# me433_test.net
KiCad netlist of a schematic drawn in EAGLE
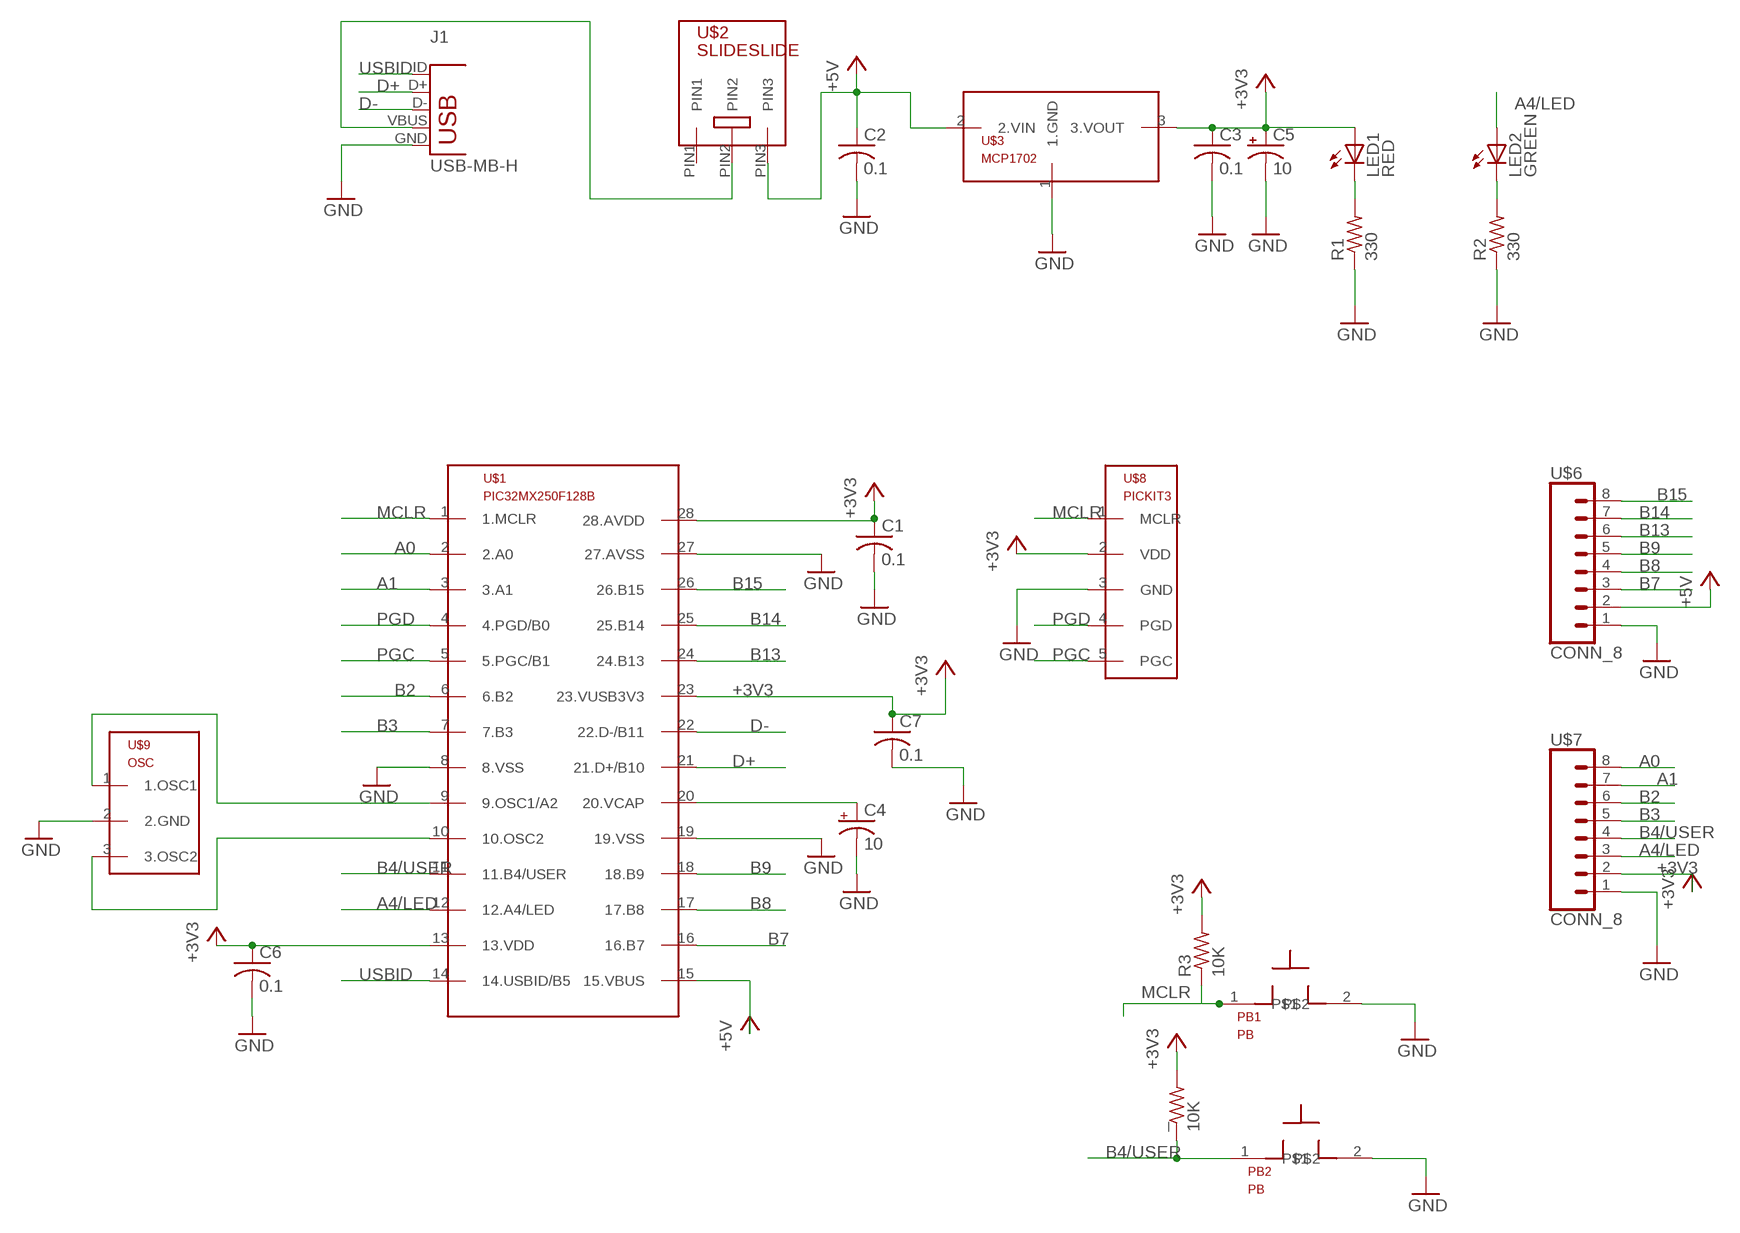
[diagram p0: schematic, sheet 1]

(export (version "E")
  (design (tool "Eeschema 10.0.6"))
  (components
    (comp (ref "C1")
      (value "0.1")
      (footprint "eagle-import:C025-025X050")
      (libsource (lib "eagle-import") (part "C-US025-025X050"))
    )
    (comp (ref "C2")
      (value "0.1")
      (footprint "eagle-import:C025-025X050")
      (libsource (lib "eagle-import") (part "C-US025-025X050"))
    )
    (comp (ref "C3")
      (value "0.1")
      (footprint "eagle-import:C025-025X050")
      (libsource (lib "eagle-import") (part "C-US025-025X050"))
    )
    (comp (ref "C4")
      (value "10")
      (footprint "eagle-import:B45181B")
      (libsource (lib "eagle-import") (part "CPOL-USB45181B"))
    )
    (comp (ref "C5")
      (value "10")
      (footprint "eagle-import:B45181B")
      (libsource (lib "eagle-import") (part "CPOL-USB45181B"))
    )
    (comp (ref "C6")
      (value "0.1")
      (footprint "eagle-import:C025-025X050")
      (libsource (lib "eagle-import") (part "C-US025-025X050"))
    )
    (comp (ref "C7")
      (value "0.1")
      (footprint "eagle-import:C025-025X050")
      (libsource (lib "eagle-import") (part "C-US025-025X050"))
    )
    (comp (ref "J1")
      (value "USB-MB-H")
      (footprint "eagle-import:USB-MB-H")
      (libsource (lib "eagle-import") (part "USB-MB-H"))
    )
    (comp (ref "LED1")
      (value "RED")
      (footprint "eagle-import:LED3MM")
      (libsource (lib "eagle-import") (part "LED3MM"))
    )
    (comp (ref "LED2")
      (value "GREEN")
      (footprint "eagle-import:LED3MM")
      (libsource (lib "eagle-import") (part "LED3MM"))
    )
    (comp (ref "PB1") (value "PB") (footprint "eagle-import:PB") (libsource (lib "eagle-import") (part "PB")))
    (comp (ref "PB2") (value "PB") (footprint "eagle-import:PB") (libsource (lib "eagle-import") (part "PB")))
    (comp (ref "R1")
      (value "330")
      (footprint "eagle-import:0207_10")
      (libsource (lib "eagle-import") (part "R-US_0207/10"))
    )
    (comp (ref "R2")
      (value "330")
      (footprint "eagle-import:0207_10")
      (libsource (lib "eagle-import") (part "R-US_0207/10"))
    )
    (comp (ref "R3")
      (value "10K")
      (footprint "eagle-import:0207_10")
      (libsource (lib "eagle-import") (part "R-US_0207/10"))
    )
    (comp (ref "U$1")
      (value "PIC32MX250F128B")
      (footprint "eagle-import:DIL28-3")
      (libsource (lib "eagle-import") (part "PIC32MX250F128B"))
    )
    (comp (ref "U$2")
      (value "SLIDESLIDE")
      (footprint "eagle-import:SLIDE")
      (libsource (lib "eagle-import") (part "SLIDESLIDE"))
    )
    (comp (ref "U$3")
      (value "MCP1702")
      (footprint "eagle-import:TO92")
      (libsource (lib "eagle-import") (part "MCP1702"))
    )
    (comp (ref "U$6")
      (value "CONN_8")
      (footprint "eagle-import:1X08")
      (libsource (lib "eagle-import") (part "CONN_8"))
    )
    (comp (ref "U$7")
      (value "CONN_8")
      (footprint "eagle-import:1X08")
      (libsource (lib "eagle-import") (part "CONN_8"))
    )
    (comp (ref "U$8")
      (value "PICKIT3")
      (footprint "eagle-import:1X05")
      (libsource (lib "eagle-import") (part "PICKIT3"))
    )
    (comp (ref "U$9")
      (value "OSC")
      (footprint "eagle-import:OSC")
      (libsource (lib "eagle-import") (part "OSC"))
    )
    (comp (ref "_")
      (value "10K")
      (footprint "eagle-import:0207_10")
      (libsource (lib "eagle-import") (part "R-US_0207/10"))
    )
  )
  (nets
    (net (code "1") (name "+3V3") (class "Default")
      (node (ref "C1") (pin "1") (pinfunction "1_1") (pintype "passive"))
      (node (ref "C3") (pin "1") (pinfunction "1_1") (pintype "passive"))
      (node (ref "C5") (pin "+") (pinfunction "+_+") (pintype "passive"))
      (node (ref "C6") (pin "1") (pinfunction "1_1") (pintype "passive"))
      (node (ref "C7") (pin "1") (pinfunction "1_1") (pintype "passive"))
      (node (ref "LED1") (pin "A") (pinfunction "A_A") (pintype "passive"))
      (node (ref "R3") (pin "2") (pinfunction "2_2") (pintype "passive"))
      (node (ref "U$1") (pin "13") (pinfunction "13.VDD_13") (pintype "bidirectional"))
      (node (ref "U$1") (pin "23") (pinfunction "23.VUSB3V3_23") (pintype "bidirectional"))
      (node (ref "U$1") (pin "28") (pinfunction "28.AVDD_28") (pintype "bidirectional"))
      (node (ref "U$3") (pin "3") (pinfunction "3.VOUT_3") (pintype "bidirectional"))
      (node (ref "U$7") (pin "2") (pinfunction "2_2") (pintype "passive"))
      (node (ref "U$8") (pin "2") (pinfunction "VDD_2") (pintype "bidirectional"))
      (node (ref "_") (pin "2") (pinfunction "2_2") (pintype "passive"))
    )
    (net (code "2") (name "+5V") (class "Default")
      (node (ref "C2") (pin "1") (pinfunction "1_1") (pintype "passive"))
      (node (ref "U$1") (pin "15") (pinfunction "15.VBUS_15") (pintype "bidirectional"))
      (node (ref "U$2") (pin "PIN3") (pinfunction "PIN3_PIN3") (pintype "bidirectional"))
      (node (ref "U$3") (pin "2") (pinfunction "2.VIN_2") (pintype "bidirectional"))
      (node (ref "U$6") (pin "2") (pinfunction "2_2") (pintype "passive"))
    )
    (net (code "3") (name "/A0") (class "Default")
      (node (ref "U$1") (pin "2") (pinfunction "2.A0_2") (pintype "bidirectional"))
      (node (ref "U$7") (pin "8") (pinfunction "8_8") (pintype "passive"))
    )
    (net (code "4") (name "/A1") (class "Default")
      (node (ref "U$1") (pin "3") (pinfunction "3.A1_3") (pintype "bidirectional"))
      (node (ref "U$7") (pin "7") (pinfunction "7_7") (pintype "passive"))
    )
    (net (code "5") (name "/A4{slash}LED") (class "Default")
      (node (ref "LED2") (pin "A") (pinfunction "A_A") (pintype "passive"))
      (node (ref "U$1") (pin "12") (pinfunction "12.A4/LED_12") (pintype "bidirectional"))
      (node (ref "U$7") (pin "3") (pinfunction "3_3") (pintype "passive"))
    )
    (net (code "6") (name "/B2") (class "Default")
      (node (ref "U$1") (pin "6") (pinfunction "6.B2_6") (pintype "bidirectional"))
      (node (ref "U$7") (pin "6") (pinfunction "6_6") (pintype "passive"))
    )
    (net (code "7") (name "/B3") (class "Default")
      (node (ref "U$1") (pin "7") (pinfunction "7.B3_7") (pintype "bidirectional"))
      (node (ref "U$7") (pin "5") (pinfunction "5_5") (pintype "passive"))
    )
    (net (code "8") (name "/B4{slash}USER") (class "Default")
      (node (ref "PB2") (pin "1") (pinfunction "P$1_1") (pintype "bidirectional"))
      (node (ref "U$1") (pin "11") (pinfunction "11.B4/USER_11") (pintype "bidirectional"))
      (node (ref "U$7") (pin "4") (pinfunction "4_4") (pintype "passive"))
      (node (ref "_") (pin "1") (pinfunction "1_1") (pintype "passive"))
    )
    (net (code "9") (name "/B7") (class "Default")
      (node (ref "U$1") (pin "16") (pinfunction "16.B7_16") (pintype "bidirectional"))
      (node (ref "U$6") (pin "3") (pinfunction "3_3") (pintype "passive"))
    )
    (net (code "10") (name "/B8") (class "Default")
      (node (ref "U$1") (pin "17") (pinfunction "17.B8_17") (pintype "bidirectional"))
      (node (ref "U$6") (pin "4") (pinfunction "4_4") (pintype "passive"))
    )
    (net (code "11") (name "/B9") (class "Default")
      (node (ref "U$1") (pin "18") (pinfunction "18.B9_18") (pintype "bidirectional"))
      (node (ref "U$6") (pin "5") (pinfunction "5_5") (pintype "passive"))
    )
    (net (code "12") (name "/B13") (class "Default")
      (node (ref "U$1") (pin "24") (pinfunction "24.B13_24") (pintype "bidirectional"))
      (node (ref "U$6") (pin "6") (pinfunction "6_6") (pintype "passive"))
    )
    (net (code "13") (name "/B14") (class "Default")
      (node (ref "U$1") (pin "25") (pinfunction "25.B14_25") (pintype "bidirectional"))
      (node (ref "U$6") (pin "7") (pinfunction "7_7") (pintype "passive"))
    )
    (net (code "14") (name "/B15") (class "Default")
      (node (ref "U$1") (pin "26") (pinfunction "26.B15_26") (pintype "bidirectional"))
      (node (ref "U$6") (pin "8") (pinfunction "8_8") (pintype "passive"))
    )
    (net (code "15") (name "/D+") (class "Default")
      (node (ref "J1") (pin "D+") (pinfunction "D+_D+") (pintype "bidirectional"))
      (node (ref "U$1") (pin "21") (pinfunction "21.D+/B10_21") (pintype "bidirectional"))
    )
    (net (code "16") (name "/D-") (class "Default")
      (node (ref "J1") (pin "D-") (pinfunction "D-_D-") (pintype "bidirectional"))
      (node (ref "U$1") (pin "22") (pinfunction "22.D-/B11_22") (pintype "bidirectional"))
    )
    (net (code "17") (name "/MCLR") (class "Default")
      (node (ref "PB1") (pin "1") (pinfunction "P$1_1") (pintype "bidirectional"))
      (node (ref "R3") (pin "1") (pinfunction "1_1") (pintype "passive"))
      (node (ref "U$1") (pin "1") (pinfunction "1.MCLR_1") (pintype "bidirectional"))
      (node (ref "U$8") (pin "1") (pinfunction "MCLR_1") (pintype "bidirectional"))
    )
    (net (code "18") (name "/PGC") (class "Default")
      (node (ref "U$1") (pin "5") (pinfunction "5.PGC/B1_5") (pintype "bidirectional"))
      (node (ref "U$8") (pin "5") (pinfunction "PGC_5") (pintype "bidirectional"))
    )
    (net (code "19") (name "/PGD") (class "Default")
      (node (ref "U$1") (pin "4") (pinfunction "4.PGD/B0_4") (pintype "bidirectional"))
      (node (ref "U$8") (pin "4") (pinfunction "PGD_4") (pintype "bidirectional"))
    )
    (net (code "20") (name "/USBID") (class "Default")
      (node (ref "J1") (pin "ID") (pinfunction "ID_ID") (pintype "bidirectional"))
      (node (ref "U$1") (pin "14") (pinfunction "14.USBID/B5_14") (pintype "bidirectional"))
    )
    (net (code "21") (name "GND") (class "Default")
      (node (ref "C1") (pin "2") (pinfunction "2_2") (pintype "passive"))
      (node (ref "C2") (pin "2") (pinfunction "2_2") (pintype "passive"))
      (node (ref "C3") (pin "2") (pinfunction "2_2") (pintype "passive"))
      (node (ref "C4") (pin "-") (pinfunction "-_-") (pintype "passive"))
      (node (ref "C5") (pin "-") (pinfunction "-_-") (pintype "passive"))
      (node (ref "C6") (pin "2") (pinfunction "2_2") (pintype "passive"))
      (node (ref "C7") (pin "2") (pinfunction "2_2") (pintype "passive"))
      (node (ref "J1") (pin "GND") (pinfunction "GND_GND") (pintype "bidirectional"))
      (node (ref "PB1") (pin "2") (pinfunction "P$2_2") (pintype "bidirectional"))
      (node (ref "PB2") (pin "2") (pinfunction "P$2_2") (pintype "bidirectional"))
      (node (ref "R1") (pin "1") (pinfunction "1_1") (pintype "passive"))
      (node (ref "R2") (pin "1") (pinfunction "1_1") (pintype "passive"))
      (node (ref "U$1") (pin "19") (pinfunction "19.VSS_19") (pintype "bidirectional"))
      (node (ref "U$1") (pin "27") (pinfunction "27.AVSS_27") (pintype "bidirectional"))
      (node (ref "U$1") (pin "8") (pinfunction "8.VSS_8") (pintype "bidirectional"))
      (node (ref "U$3") (pin "1") (pinfunction "1.GND_1") (pintype "bidirectional"))
      (node (ref "U$6") (pin "1") (pinfunction "1_1") (pintype "passive"))
      (node (ref "U$7") (pin "1") (pinfunction "1_1") (pintype "passive"))
      (node (ref "U$8") (pin "3") (pinfunction "GND_3") (pintype "bidirectional"))
      (node (ref "U$9") (pin "2") (pinfunction "2.GND_2") (pintype "bidirectional"))
    )
    (net (code "22") (name "Net-(J1-PadVBUS)") (class "Default")
      (node (ref "J1") (pin "VBUS") (pinfunction "VBUS_VBUS") (pintype "bidirectional"))
      (node (ref "U$2") (pin "PIN2") (pinfunction "PIN2_PIN2") (pintype "bidirectional"))
    )
    (net (code "23") (name "Net-(LED1-C)") (class "Default")
      (node (ref "LED1") (pin "K") (pinfunction "C_K") (pintype "passive"))
      (node (ref "R1") (pin "2") (pinfunction "2_2") (pintype "passive"))
    )
    (net (code "24") (name "Net-(LED2-C)") (class "Default")
      (node (ref "LED2") (pin "K") (pinfunction "C_K") (pintype "passive"))
      (node (ref "R2") (pin "2") (pinfunction "2_2") (pintype "passive"))
    )
    (net (code "25") (name "Net-(U$1-9.OSC1{slash}A2)") (class "Default")
      (node (ref "U$1") (pin "9") (pinfunction "9.OSC1/A2_9") (pintype "bidirectional"))
      (node (ref "U$9") (pin "1") (pinfunction "1.OSC1_1") (pintype "bidirectional"))
    )
    (net (code "26") (name "Net-(U$1-10.OSC2)") (class "Default")
      (node (ref "U$1") (pin "10") (pinfunction "10.OSC2_10") (pintype "bidirectional"))
      (node (ref "U$9") (pin "3") (pinfunction "3.OSC2_3") (pintype "bidirectional"))
    )
    (net (code "27") (name "Net-(U$1-20.VCAP)") (class "Default")
      (node (ref "C4") (pin "+") (pinfunction "+_+") (pintype "passive"))
      (node (ref "U$1") (pin "20") (pinfunction "20.VCAP_20") (pintype "bidirectional"))
    )
    (net (code "28") (name "unconnected-(U$2-PadPIN1)") (class "Default")
      (node (ref "U$2") (pin "PIN1") (pinfunction "PIN1_PIN1") (pintype "bidirectional"))
    )
  )
)
